# stm32uni.net
KiCad netlist of a schematic drawn in EAGLE
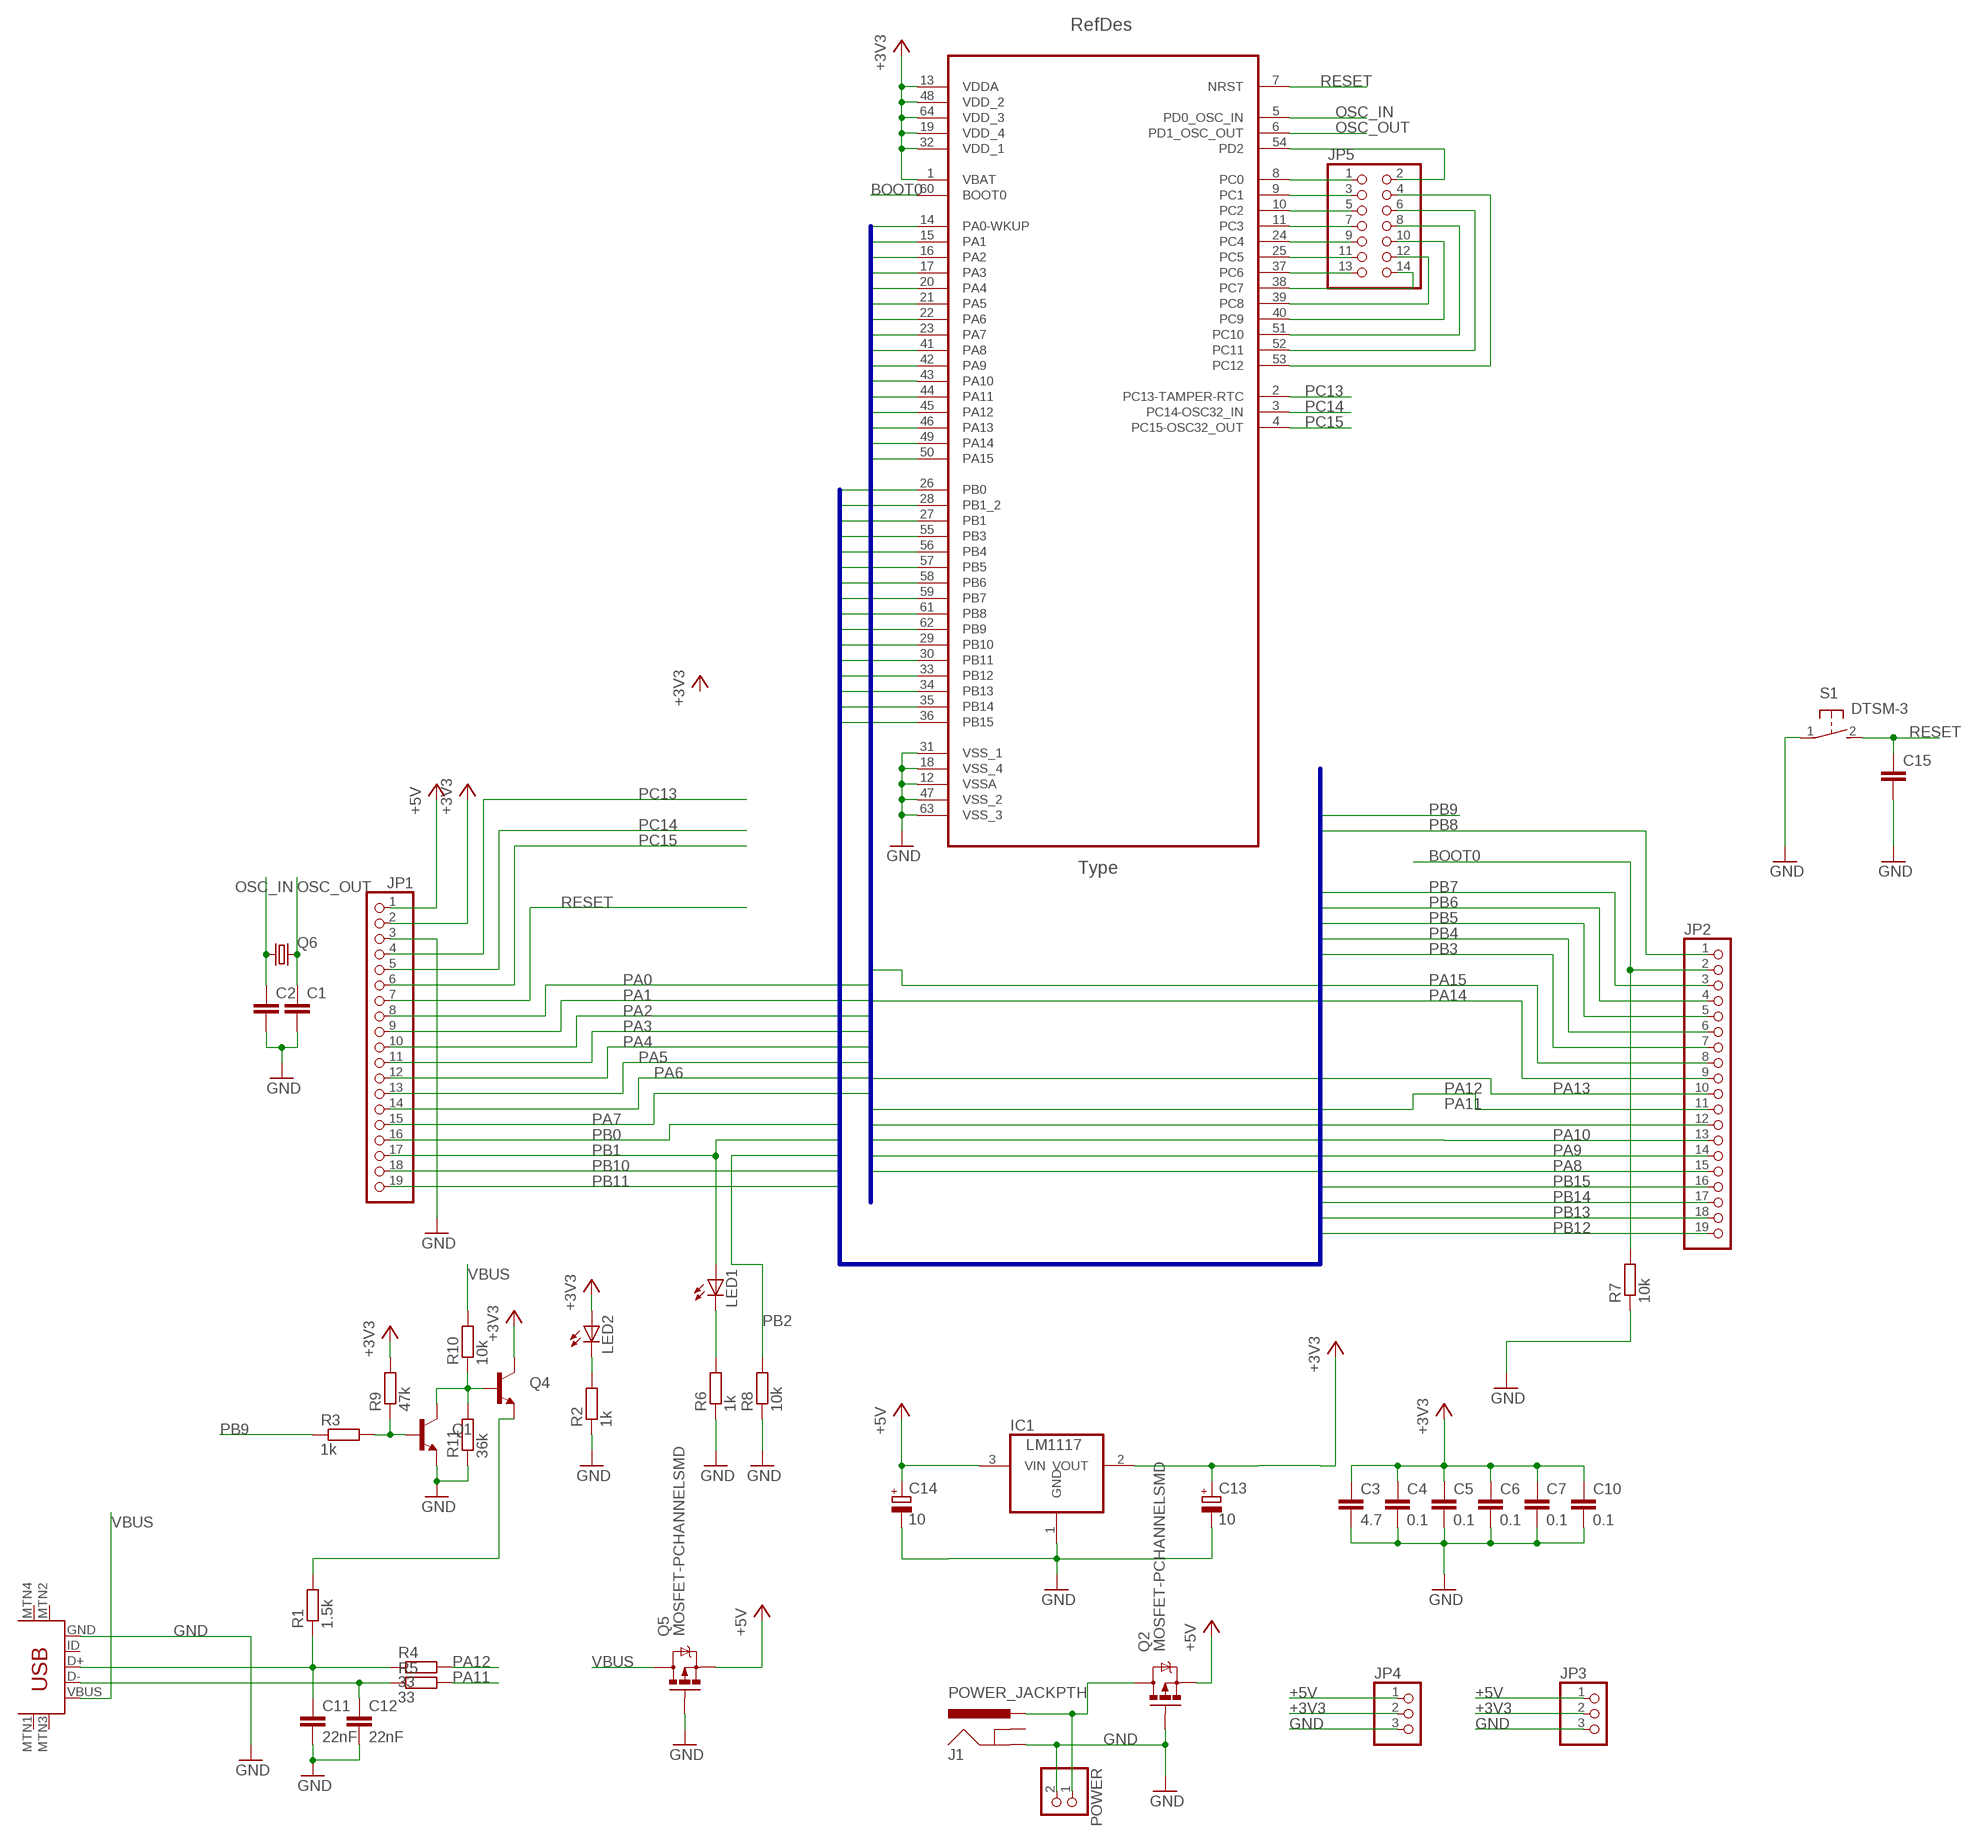
[diagram p0: schematic, sheet 1]

(export (version "E")
  (design (tool "Eeschema 10.0.6"))
  (components
    (comp (ref "C1")
      (value "C-EUC0805")
      (footprint "eagle-import:C0805")
      (libsource (lib "eagle-import") (part "C-EUC0805"))
    )
    (comp (ref "C2")
      (value "C-EUC0805")
      (footprint "eagle-import:C0805")
      (libsource (lib "eagle-import") (part "C-EUC0805"))
    )
    (comp (ref "C3")
      (value "4.7")
      (footprint "eagle-import:C0805")
      (libsource (lib "eagle-import") (part "C-EUC0805"))
    )
    (comp (ref "C4")
      (value "0.1")
      (footprint "eagle-import:C0805")
      (libsource (lib "eagle-import") (part "C-EUC0805"))
    )
    (comp (ref "C5")
      (value "0.1")
      (footprint "eagle-import:C0805")
      (libsource (lib "eagle-import") (part "C-EUC0805"))
    )
    (comp (ref "C6")
      (value "0.1")
      (footprint "eagle-import:C0805")
      (libsource (lib "eagle-import") (part "C-EUC0805"))
    )
    (comp (ref "C7")
      (value "0.1")
      (footprint "eagle-import:C0805")
      (libsource (lib "eagle-import") (part "C-EUC0805"))
    )
    (comp (ref "C10")
      (value "0.1")
      (footprint "eagle-import:C0805")
      (libsource (lib "eagle-import") (part "C-EUC0805"))
    )
    (comp (ref "C11")
      (value "22nF")
      (footprint "eagle-import:C0805")
      (libsource (lib "eagle-import") (part "C-EUC0805"))
    )
    (comp (ref "C12")
      (value "22nF")
      (footprint "eagle-import:C0805")
      (libsource (lib "eagle-import") (part "C-EUC0805"))
    )
    (comp (ref "C13")
      (value "10")
      (footprint "eagle-import:SMC_B")
      (libsource (lib "eagle-import") (part "CPOL-EUSMCB"))
    )
    (comp (ref "C14")
      (value "10")
      (footprint "eagle-import:SMC_B")
      (libsource (lib "eagle-import") (part "CPOL-EUSMCB"))
    )
    (comp (ref "C15")
      (value "C-EUC0805")
      (footprint "eagle-import:C0805")
      (libsource (lib "eagle-import") (part "C-EUC0805"))
    )
    (comp (ref "IC1")
      (value "LM1117")
      (footprint "eagle-import:SOT223")
      (fields (field (name "MPN") "REG1117"))
      (libsource (lib "eagle-import") (part "REG1117"))
    )
    (comp (ref "J1")
      (value "POWER_JACKPTH")
      (footprint "eagle-import:POWER_JACK_PTH")
      (libsource (lib "eagle-import") (part "POWER_JACKPTH"))
    )
    (comp (ref "JP1")
      (value "PINHD-1X19")
      (footprint "eagle-import:1X19")
      (libsource (lib "eagle-import") (part "PINHD-1X19"))
    )
    (comp (ref "JP2")
      (value "PINHD-1X19")
      (footprint "eagle-import:1X19")
      (libsource (lib "eagle-import") (part "PINHD-1X19"))
    )
    (comp (ref "JP3")
      (value "PINHD-1X3")
      (footprint "eagle-import:1X03")
      (libsource (lib "eagle-import") (part "PINHD-1X3"))
    )
    (comp (ref "JP4")
      (value "PINHD-1X3")
      (footprint "eagle-import:1X03")
      (libsource (lib "eagle-import") (part "PINHD-1X3"))
    )
    (comp (ref "JP5")
      (value "PINHD-2X7")
      (footprint "eagle-import:2X07")
      (libsource (lib "eagle-import") (part "PINHD-2X7"))
    )
    (comp (ref "LED1")
      (value "LEDCHIPLED_0805")
      (footprint "eagle-import:CHIPLED_0805")
      (libsource (lib "eagle-import") (part "LEDCHIPLED_0805"))
    )
    (comp (ref "LED2")
      (value "LEDCHIPLED_0805")
      (footprint "eagle-import:CHIPLED_0805")
      (libsource (lib "eagle-import") (part "LEDCHIPLED_0805"))
    )
    (comp (ref "POWER")
      (value "PINHD-1X2")
      (footprint "eagle-import:1X02")
      (libsource (lib "eagle-import") (part "PINHD-1X2"))
    )
    (comp (ref "Q1")
      (value "TRANSISTOR_NPNSOT23")
      (footprint "eagle-import:SOT23")
      (libsource (lib "eagle-import") (part "TRANSISTOR_NPNSOT23"))
    )
    (comp (ref "Q2")
      (value "MOSFET-PCHANNELSMD")
      (footprint "eagle-import:SOT23-3")
      (libsource (lib "eagle-import") (part "MOSFET-PCHANNELSMD"))
    )
    (comp (ref "Q4")
      (value "TRANSISTOR_NPNSOT23")
      (footprint "eagle-import:SOT23")
      (libsource (lib "eagle-import") (part "TRANSISTOR_NPNSOT23"))
    )
    (comp (ref "Q5")
      (value "MOSFET-PCHANNELSMD")
      (footprint "eagle-import:SOT23-3")
      (libsource (lib "eagle-import") (part "MOSFET-PCHANNELSMD"))
    )
    (comp (ref "Q6")
      (value "CRYSTALSM49")
      (footprint "eagle-import:SM49")
      (libsource (lib "eagle-import") (part "CRYSTALSM49"))
    )
    (comp (ref "R1")
      (value "1.5k")
      (footprint "eagle-import:R0805")
      (libsource (lib "eagle-import") (part "R-EU_R0805"))
    )
    (comp (ref "R2")
      (value "1k")
      (footprint "eagle-import:R0805")
      (libsource (lib "eagle-import") (part "R-EU_R0805"))
    )
    (comp (ref "R3")
      (value "1k")
      (footprint "eagle-import:R0805")
      (libsource (lib "eagle-import") (part "R-EU_R0805"))
    )
    (comp (ref "R4")
      (value "33")
      (footprint "eagle-import:R0805")
      (libsource (lib "eagle-import") (part "R-EU_R0805"))
    )
    (comp (ref "R5")
      (value "33")
      (footprint "eagle-import:R0805")
      (libsource (lib "eagle-import") (part "R-EU_R0805"))
    )
    (comp (ref "R6")
      (value "1k")
      (footprint "eagle-import:R0805")
      (libsource (lib "eagle-import") (part "R-EU_R0805"))
    )
    (comp (ref "R7")
      (value "10k")
      (footprint "eagle-import:R0805")
      (libsource (lib "eagle-import") (part "R-EU_R0805"))
    )
    (comp (ref "R8")
      (value "10k")
      (footprint "eagle-import:R0805")
      (libsource (lib "eagle-import") (part "R-EU_R0805"))
    )
    (comp (ref "R9")
      (value "47k")
      (footprint "eagle-import:R0805")
      (libsource (lib "eagle-import") (part "R-EU_R0805"))
    )
    (comp (ref "R10")
      (value "10k")
      (footprint "eagle-import:R0805")
      (libsource (lib "eagle-import") (part "R-EU_R0805"))
    )
    (comp (ref "R11")
      (value "36k")
      (footprint "eagle-import:R0805")
      (libsource (lib "eagle-import") (part "R-EU_R0805"))
    )
    (comp (ref "S1")
      (value "DTSM-3")
      (footprint "eagle-import:DTSM-3")
      (libsource (lib "eagle-import") (part "DTSM-3"))
    )
    (comp (ref "U$1")
      (value "USB-MINIB-5PIN")
      (footprint "eagle-import:USB-MINIB")
      (libsource (lib "eagle-import") (part "USB-MINIB-5PIN"))
    )
    (comp (ref "U1")
      (value "STM32F103RET6")
      (footprint "eagle-import:QFP50P1200X1200X160-64N")
      (libsource (lib "eagle-import") (part "STM32F103RET6"))
    )
  )
  (nets
    (net (code "1") (name "+3V3") (class "Default")
      (node (ref "C10") (pin "1") (pinfunction "1_1") (pintype "passive"))
      (node (ref "C13") (pin "+") (pinfunction "+_+") (pintype "passive"))
      (node (ref "C3") (pin "1") (pinfunction "1_1") (pintype "passive"))
      (node (ref "C4") (pin "1") (pinfunction "1_1") (pintype "passive"))
      (node (ref "C5") (pin "1") (pinfunction "1_1") (pintype "passive"))
      (node (ref "C6") (pin "1") (pinfunction "1_1") (pintype "passive"))
      (node (ref "C7") (pin "1") (pinfunction "1_1") (pintype "passive"))
      (node (ref "IC1") (pin "2") (pinfunction "VOUT_2") (pintype "output"))
      (node (ref "JP1") (pin "2") (pinfunction "2_2") (pintype "passive"))
      (node (ref "JP3") (pin "2") (pinfunction "2_2") (pintype "passive"))
      (node (ref "JP4") (pin "2") (pinfunction "2_2") (pintype "passive"))
      (node (ref "LED2") (pin "A") (pinfunction "A_A") (pintype "passive"))
      (node (ref "Q4") (pin "3") (pinfunction "C_3") (pintype "passive"))
      (node (ref "R9") (pin "2") (pinfunction "2_2") (pintype "passive"))
      (node (ref "U1") (pin "1") (pinfunction "VBAT_1") (pintype "input"))
      (node (ref "U1") (pin "13") (pinfunction "VDDA_13") (pintype "power_in"))
      (node (ref "U1") (pin "19") (pinfunction "VDD_4_19") (pintype "power_in"))
      (node (ref "U1") (pin "32") (pinfunction "VDD_1_32") (pintype "power_in"))
      (node (ref "U1") (pin "48") (pinfunction "VDD_2_48") (pintype "power_in"))
      (node (ref "U1") (pin "64") (pinfunction "VDD_3_64") (pintype "power_in"))
    )
    (net (code "2") (name "+5V") (class "Default")
      (node (ref "C14") (pin "+") (pinfunction "+_+") (pintype "passive"))
      (node (ref "IC1") (pin "3") (pinfunction "VIN_3") (pintype "input"))
      (node (ref "JP1") (pin "1") (pinfunction "1_1") (pintype "passive"))
      (node (ref "JP3") (pin "1") (pinfunction "1_1") (pintype "passive"))
      (node (ref "JP4") (pin "1") (pinfunction "1_1") (pintype "passive"))
      (node (ref "Q2") (pin "2") (pinfunction "S_2") (pintype "passive"))
      (node (ref "Q5") (pin "2") (pinfunction "S_2") (pintype "passive"))
    )
    (net (code "3") (name "/BOOT0") (class "Default")
      (node (ref "JP2") (pin "2") (pinfunction "2_2") (pintype "passive"))
      (node (ref "R7") (pin "2") (pinfunction "2_2") (pintype "passive"))
      (node (ref "U1") (pin "60") (pinfunction "BOOT0_60") (pintype "passive"))
    )
    (net (code "4") (name "/OSC_IN") (class "Default")
      (node (ref "C2") (pin "1") (pinfunction "1_1") (pintype "passive"))
      (node (ref "Q6") (pin "1") (pinfunction "1_1") (pintype "passive"))
      (node (ref "U1") (pin "5") (pinfunction "PD0_OSC_IN_5") (pintype "input"))
    )
    (net (code "5") (name "/OSC_OUT") (class "Default")
      (node (ref "C1") (pin "1") (pinfunction "1_1") (pintype "passive"))
      (node (ref "Q6") (pin "2") (pinfunction "2_2") (pintype "passive"))
      (node (ref "U1") (pin "6") (pinfunction "PD1_OSC_OUT_6") (pintype "output"))
    )
    (net (code "6") (name "/PA0") (class "Default")
      (node (ref "JP1") (pin "8") (pinfunction "8_8") (pintype "passive"))
      (node (ref "U1") (pin "14") (pinfunction "PA0-WKUP_14") (pintype "bidirectional"))
    )
    (net (code "7") (name "/PA1") (class "Default")
      (node (ref "JP1") (pin "9") (pinfunction "9_9") (pintype "passive"))
      (node (ref "U1") (pin "15") (pinfunction "PA1_15") (pintype "bidirectional"))
    )
    (net (code "8") (name "/PA2") (class "Default")
      (node (ref "JP1") (pin "10") (pinfunction "10_10") (pintype "passive"))
      (node (ref "U1") (pin "16") (pinfunction "PA2_16") (pintype "bidirectional"))
    )
    (net (code "9") (name "/PA3") (class "Default")
      (node (ref "JP1") (pin "11") (pinfunction "11_11") (pintype "passive"))
      (node (ref "U1") (pin "17") (pinfunction "PA3_17") (pintype "bidirectional"))
    )
    (net (code "10") (name "/PA4") (class "Default")
      (node (ref "JP1") (pin "12") (pinfunction "12_12") (pintype "passive"))
      (node (ref "U1") (pin "20") (pinfunction "PA4_20") (pintype "bidirectional"))
    )
    (net (code "11") (name "/PA5") (class "Default")
      (node (ref "JP1") (pin "13") (pinfunction "13_13") (pintype "passive"))
      (node (ref "U1") (pin "21") (pinfunction "PA5_21") (pintype "bidirectional"))
    )
    (net (code "12") (name "/PA6") (class "Default")
      (node (ref "JP1") (pin "14") (pinfunction "14_14") (pintype "passive"))
      (node (ref "U1") (pin "22") (pinfunction "PA6_22") (pintype "bidirectional"))
    )
    (net (code "13") (name "/PA7") (class "Default")
      (node (ref "JP1") (pin "15") (pinfunction "15_15") (pintype "passive"))
      (node (ref "U1") (pin "23") (pinfunction "PA7_23") (pintype "power_in"))
    )
    (net (code "14") (name "/PA8") (class "Default")
      (node (ref "JP2") (pin "15") (pinfunction "15_15") (pintype "passive"))
      (node (ref "U1") (pin "41") (pinfunction "PA8_41") (pintype "bidirectional"))
    )
    (net (code "15") (name "/PA9") (class "Default")
      (node (ref "JP2") (pin "14") (pinfunction "14_14") (pintype "passive"))
      (node (ref "U1") (pin "42") (pinfunction "PA9_42") (pintype "bidirectional"))
    )
    (net (code "16") (name "/PA10") (class "Default")
      (node (ref "JP2") (pin "13") (pinfunction "13_13") (pintype "passive"))
      (node (ref "U1") (pin "43") (pinfunction "PA10_43") (pintype "bidirectional"))
    )
    (net (code "17") (name "/PA11") (class "Default")
      (node (ref "JP2") (pin "12") (pinfunction "12_12") (pintype "passive"))
      (node (ref "R5") (pin "2") (pinfunction "2_2") (pintype "passive"))
      (node (ref "U1") (pin "44") (pinfunction "PA11_44") (pintype "bidirectional"))
    )
    (net (code "18") (name "/PA12") (class "Default")
      (node (ref "JP2") (pin "11") (pinfunction "11_11") (pintype "passive"))
      (node (ref "R4") (pin "2") (pinfunction "2_2") (pintype "passive"))
      (node (ref "U1") (pin "45") (pinfunction "PA12_45") (pintype "bidirectional"))
    )
    (net (code "19") (name "/PA13") (class "Default")
      (node (ref "JP2") (pin "10") (pinfunction "10_10") (pintype "passive"))
      (node (ref "U1") (pin "46") (pinfunction "PA13_46") (pintype "bidirectional"))
    )
    (net (code "20") (name "/PA14") (class "Default")
      (node (ref "JP2") (pin "9") (pinfunction "9_9") (pintype "passive"))
      (node (ref "U1") (pin "49") (pinfunction "PA14_49") (pintype "bidirectional"))
    )
    (net (code "21") (name "/PA15") (class "Default")
      (node (ref "JP2") (pin "8") (pinfunction "8_8") (pintype "passive"))
      (node (ref "U1") (pin "50") (pinfunction "PA15_50") (pintype "bidirectional"))
    )
    (net (code "22") (name "/PB0") (class "Default")
      (node (ref "JP1") (pin "16") (pinfunction "16_16") (pintype "passive"))
      (node (ref "U1") (pin "26") (pinfunction "PB0_26") (pintype "bidirectional"))
    )
    (net (code "23") (name "/PB1") (class "Default")
      (node (ref "JP1") (pin "17") (pinfunction "17_17") (pintype "passive"))
      (node (ref "LED1") (pin "A") (pinfunction "A_A") (pintype "passive"))
      (node (ref "U1") (pin "27") (pinfunction "PB1_27") (pintype "bidirectional"))
    )
    (net (code "24") (name "/PB2") (class "Default")
      (node (ref "R8") (pin "2") (pinfunction "2_2") (pintype "passive"))
      (node (ref "U1") (pin "28") (pinfunction "PB1_2_28") (pintype "bidirectional"))
    )
    (net (code "25") (name "/PB3") (class "Default")
      (node (ref "JP2") (pin "7") (pinfunction "7_7") (pintype "passive"))
      (node (ref "U1") (pin "55") (pinfunction "PB3_55") (pintype "bidirectional"))
    )
    (net (code "26") (name "/PB4") (class "Default")
      (node (ref "JP2") (pin "6") (pinfunction "6_6") (pintype "passive"))
      (node (ref "U1") (pin "56") (pinfunction "PB4_56") (pintype "bidirectional"))
    )
    (net (code "27") (name "/PB5") (class "Default")
      (node (ref "JP2") (pin "5") (pinfunction "5_5") (pintype "passive"))
      (node (ref "U1") (pin "57") (pinfunction "PB5_57") (pintype "bidirectional"))
    )
    (net (code "28") (name "/PB6") (class "Default")
      (node (ref "JP2") (pin "4") (pinfunction "4_4") (pintype "passive"))
      (node (ref "U1") (pin "58") (pinfunction "PB6_58") (pintype "bidirectional"))
    )
    (net (code "29") (name "/PB7") (class "Default")
      (node (ref "JP2") (pin "3") (pinfunction "3_3") (pintype "passive"))
      (node (ref "U1") (pin "59") (pinfunction "PB7_59") (pintype "power_in"))
    )
    (net (code "30") (name "/PB8") (class "Default")
      (node (ref "JP2") (pin "1") (pinfunction "1_1") (pintype "passive"))
      (node (ref "U1") (pin "61") (pinfunction "PB8_61") (pintype "bidirectional"))
    )
    (net (code "31") (name "/PB9") (class "Default")
      (node (ref "R3") (pin "1") (pinfunction "1_1") (pintype "passive"))
      (node (ref "U1") (pin "62") (pinfunction "PB9_62") (pintype "bidirectional"))
    )
    (net (code "32") (name "/PB10") (class "Default")
      (node (ref "JP1") (pin "18") (pinfunction "18_18") (pintype "passive"))
      (node (ref "U1") (pin "29") (pinfunction "PB10_29") (pintype "bidirectional"))
    )
    (net (code "33") (name "/PB11") (class "Default")
      (node (ref "JP1") (pin "19") (pinfunction "19_19") (pintype "passive"))
      (node (ref "U1") (pin "30") (pinfunction "PB11_30") (pintype "bidirectional"))
    )
    (net (code "34") (name "/PB12") (class "Default")
      (node (ref "JP2") (pin "19") (pinfunction "19_19") (pintype "passive"))
      (node (ref "U1") (pin "33") (pinfunction "PB12_33") (pintype "bidirectional"))
    )
    (net (code "35") (name "/PB13") (class "Default")
      (node (ref "JP2") (pin "18") (pinfunction "18_18") (pintype "passive"))
      (node (ref "U1") (pin "34") (pinfunction "PB13_34") (pintype "bidirectional"))
    )
    (net (code "36") (name "/PB14") (class "Default")
      (node (ref "JP2") (pin "17") (pinfunction "17_17") (pintype "passive"))
      (node (ref "U1") (pin "35") (pinfunction "PB14_35") (pintype "bidirectional"))
    )
    (net (code "37") (name "/PB15") (class "Default")
      (node (ref "JP2") (pin "16") (pinfunction "16_16") (pintype "passive"))
      (node (ref "U1") (pin "36") (pinfunction "PB15_36") (pintype "bidirectional"))
    )
    (net (code "38") (name "/PC13") (class "Default")
      (node (ref "JP1") (pin "4") (pinfunction "4_4") (pintype "passive"))
      (node (ref "U1") (pin "2") (pinfunction "PC13-TAMPER-RTC_2") (pintype "input"))
    )
    (net (code "39") (name "/PC14") (class "Default")
      (node (ref "JP1") (pin "5") (pinfunction "5_5") (pintype "passive"))
      (node (ref "U1") (pin "3") (pinfunction "PC14-OSC32_IN_3") (pintype "input"))
    )
    (net (code "40") (name "/PC15") (class "Default")
      (node (ref "JP1") (pin "6") (pinfunction "6_6") (pintype "passive"))
      (node (ref "U1") (pin "4") (pinfunction "PC15-OSC32_OUT_4") (pintype "output"))
    )
    (net (code "41") (name "/RESET") (class "Default")
      (node (ref "C15") (pin "1") (pinfunction "1_1") (pintype "passive"))
      (node (ref "JP1") (pin "7") (pinfunction "7_7") (pintype "passive"))
      (node (ref "S1") (pin "2") (pinfunction "2_2") (pintype "passive"))
      (node (ref "U1") (pin "7") (pinfunction "NRST_7") (pintype "output"))
    )
    (net (code "42") (name "/VBUS") (class "Default")
      (node (ref "Q5") (pin "3") (pinfunction "D_3") (pintype "passive"))
      (node (ref "R10") (pin "2") (pinfunction "2_2") (pintype "passive"))
      (node (ref "U$1") (pin "VBUS") (pinfunction "VBUS_VBUS") (pintype "bidirectional"))
    )
    (net (code "43") (name "GND") (class "Default")
      (node (ref "C1") (pin "2") (pinfunction "2_2") (pintype "passive"))
      (node (ref "C10") (pin "2") (pinfunction "2_2") (pintype "passive"))
      (node (ref "C11") (pin "2") (pinfunction "2_2") (pintype "passive"))
      (node (ref "C12") (pin "2") (pinfunction "2_2") (pintype "passive"))
      (node (ref "C13") (pin "-") (pinfunction "-_-") (pintype "passive"))
      (node (ref "C14") (pin "-") (pinfunction "-_-") (pintype "passive"))
      (node (ref "C15") (pin "2") (pinfunction "2_2") (pintype "passive"))
      (node (ref "C2") (pin "2") (pinfunction "2_2") (pintype "passive"))
      (node (ref "C3") (pin "2") (pinfunction "2_2") (pintype "passive"))
      (node (ref "C4") (pin "2") (pinfunction "2_2") (pintype "passive"))
      (node (ref "C5") (pin "2") (pinfunction "2_2") (pintype "passive"))
      (node (ref "C6") (pin "2") (pinfunction "2_2") (pintype "passive"))
      (node (ref "C7") (pin "2") (pinfunction "2_2") (pintype "passive"))
      (node (ref "IC1") (pin "1") (pinfunction "GND_1") (pintype "power_in"))
      (node (ref "J1") (pin "GND") (pinfunction "GND_GND") (pintype "bidirectional"))
      (node (ref "JP1") (pin "3") (pinfunction "3_3") (pintype "passive"))
      (node (ref "JP3") (pin "3") (pinfunction "3_3") (pintype "passive"))
      (node (ref "JP4") (pin "3") (pinfunction "3_3") (pintype "passive"))
      (node (ref "POWER") (pin "2") (pinfunction "2_2") (pintype "passive"))
      (node (ref "Q1") (pin "2") (pinfunction "E_2") (pintype "passive"))
      (node (ref "Q2") (pin "1") (pinfunction "G_1") (pintype "passive"))
      (node (ref "Q5") (pin "1") (pinfunction "G_1") (pintype "passive"))
      (node (ref "R11") (pin "1") (pinfunction "1_1") (pintype "passive"))
      (node (ref "R2") (pin "1") (pinfunction "1_1") (pintype "passive"))
      (node (ref "R6") (pin "1") (pinfunction "1_1") (pintype "passive"))
      (node (ref "R7") (pin "1") (pinfunction "1_1") (pintype "passive"))
      (node (ref "R8") (pin "1") (pinfunction "1_1") (pintype "passive"))
      (node (ref "S1") (pin "1") (pinfunction "1_1") (pintype "passive"))
      (node (ref "U$1") (pin "GND") (pinfunction "GND_GND") (pintype "bidirectional"))
      (node (ref "U1") (pin "12") (pinfunction "VSSA_12") (pintype "passive"))
      (node (ref "U1") (pin "18") (pinfunction "VSS_4_18") (pintype "passive"))
      (node (ref "U1") (pin "31") (pinfunction "VSS_1_31") (pintype "passive"))
      (node (ref "U1") (pin "47") (pinfunction "VSS_2_47") (pintype "passive"))
      (node (ref "U1") (pin "63") (pinfunction "VSS_3_63") (pintype "passive"))
    )
    (net (code "44") (name "Net-(C11-Pad1)") (class "Default")
      (node (ref "C11") (pin "1") (pinfunction "1_1") (pintype "passive"))
      (node (ref "R1") (pin "1") (pinfunction "1_1") (pintype "passive"))
      (node (ref "R4") (pin "1") (pinfunction "1_1") (pintype "passive"))
      (node (ref "U$1") (pin "D+") (pinfunction "D+_D+") (pintype "bidirectional"))
    )
    (net (code "45") (name "Net-(C12-Pad1)") (class "Default")
      (node (ref "C12") (pin "1") (pinfunction "1_1") (pintype "passive"))
      (node (ref "R5") (pin "1") (pinfunction "1_1") (pintype "passive"))
      (node (ref "U$1") (pin "D-") (pinfunction "D-_D-") (pintype "bidirectional"))
    )
    (net (code "46") (name "Net-(LED1-PadC)") (class "Default")
      (node (ref "LED1") (pin "C") (pinfunction "C_C") (pintype "passive"))
      (node (ref "R6") (pin "2") (pinfunction "2_2") (pintype "passive"))
    )
    (net (code "47") (name "Net-(LED2-PadC)") (class "Default")
      (node (ref "LED2") (pin "C") (pinfunction "C_C") (pintype "passive"))
      (node (ref "R2") (pin "2") (pinfunction "2_2") (pintype "passive"))
    )
    (net (code "48") (name "Net-(Q1-B)") (class "Default")
      (node (ref "Q1") (pin "1") (pinfunction "B_1") (pintype "passive"))
      (node (ref "R3") (pin "2") (pinfunction "2_2") (pintype "passive"))
      (node (ref "R9") (pin "1") (pinfunction "1_1") (pintype "passive"))
    )
    (net (code "49") (name "Net-(Q1-C)") (class "Default")
      (node (ref "Q1") (pin "3") (pinfunction "C_3") (pintype "passive"))
      (node (ref "Q4") (pin "1") (pinfunction "B_1") (pintype "passive"))
      (node (ref "R10") (pin "1") (pinfunction "1_1") (pintype "passive"))
      (node (ref "R11") (pin "2") (pinfunction "2_2") (pintype "passive"))
    )
    (net (code "50") (name "Net-(Q2-D)") (class "Default")
      (node (ref "J1") (pin "PWR") (pinfunction "PWR_PWR") (pintype "bidirectional"))
      (node (ref "POWER") (pin "1") (pinfunction "1_1") (pintype "passive"))
      (node (ref "Q2") (pin "3") (pinfunction "D_3") (pintype "passive"))
    )
    (net (code "51") (name "Net-(Q4-E)") (class "Default")
      (node (ref "Q4") (pin "2") (pinfunction "E_2") (pintype "passive"))
      (node (ref "R1") (pin "2") (pinfunction "2_2") (pintype "passive"))
    )
    (net (code "52") (name "Net-(U1-PC0)") (class "Default")
      (node (ref "JP5") (pin "1") (pinfunction "1_1") (pintype "passive"))
      (node (ref "U1") (pin "8") (pinfunction "PC0_8") (pintype "bidirectional"))
    )
    (net (code "53") (name "Net-(U1-PC1)") (class "Default")
      (node (ref "JP5") (pin "3") (pinfunction "3_3") (pintype "passive"))
      (node (ref "U1") (pin "9") (pinfunction "PC1_9") (pintype "bidirectional"))
    )
    (net (code "54") (name "Net-(U1-PC2)") (class "Default")
      (node (ref "JP5") (pin "5") (pinfunction "5_5") (pintype "passive"))
      (node (ref "U1") (pin "10") (pinfunction "PC2_10") (pintype "bidirectional"))
    )
    (net (code "55") (name "Net-(U1-PC3)") (class "Default")
      (node (ref "JP5") (pin "7") (pinfunction "7_7") (pintype "passive"))
      (node (ref "U1") (pin "11") (pinfunction "PC3_11") (pintype "bidirectional"))
    )
    (net (code "56") (name "Net-(U1-PC4)") (class "Default")
      (node (ref "JP5") (pin "9") (pinfunction "9_9") (pintype "passive"))
      (node (ref "U1") (pin "24") (pinfunction "PC4_24") (pintype "passive"))
    )
    (net (code "57") (name "Net-(U1-PC5)") (class "Default")
      (node (ref "JP5") (pin "11") (pinfunction "11_11") (pintype "passive"))
      (node (ref "U1") (pin "25") (pinfunction "PC5_25") (pintype "bidirectional"))
    )
    (net (code "58") (name "Net-(U1-PC6)") (class "Default")
      (node (ref "JP5") (pin "13") (pinfunction "13_13") (pintype "passive"))
      (node (ref "U1") (pin "37") (pinfunction "PC6_37") (pintype "bidirectional"))
    )
    (net (code "59") (name "Net-(U1-PC7)") (class "Default")
      (node (ref "JP5") (pin "14") (pinfunction "14_14") (pintype "passive"))
      (node (ref "U1") (pin "38") (pinfunction "PC7_38") (pintype "bidirectional"))
    )
    (net (code "60") (name "Net-(U1-PC8)") (class "Default")
      (node (ref "JP5") (pin "12") (pinfunction "12_12") (pintype "passive"))
      (node (ref "U1") (pin "39") (pinfunction "PC8_39") (pintype "bidirectional"))
    )
    (net (code "61") (name "Net-(U1-PC9)") (class "Default")
      (node (ref "JP5") (pin "10") (pinfunction "10_10") (pintype "passive"))
      (node (ref "U1") (pin "40") (pinfunction "PC9_40") (pintype "bidirectional"))
    )
    (net (code "62") (name "Net-(U1-PC10)") (class "Default")
      (node (ref "JP5") (pin "8") (pinfunction "8_8") (pintype "passive"))
      (node (ref "U1") (pin "51") (pinfunction "PC10_51") (pintype "bidirectional"))
    )
    (net (code "63") (name "Net-(U1-PC11)") (class "Default")
      (node (ref "JP5") (pin "6") (pinfunction "6_6") (pintype "passive"))
      (node (ref "U1") (pin "52") (pinfunction "PC11_52") (pintype "bidirectional"))
    )
    (net (code "64") (name "Net-(U1-PC12)") (class "Default")
      (node (ref "JP5") (pin "4") (pinfunction "4_4") (pintype "passive"))
      (node (ref "U1") (pin "53") (pinfunction "PC12_53") (pintype "bidirectional"))
    )
    (net (code "65") (name "Net-(U1-PD2)") (class "Default")
      (node (ref "JP5") (pin "2") (pinfunction "2_2") (pintype "passive"))
      (node (ref "U1") (pin "54") (pinfunction "PD2_54") (pintype "bidirectional"))
    )
    (net (code "66") (name "unconnected-(J1-PadGNDBREAK)") (class "Default")
      (node (ref "J1") (pin "GNDBREAK") (pinfunction "GNDBREAK_GNDBREAK") (pintype "bidirectional"))
    )
    (net (code "67") (name "unconnected-(U$1-MTN1-PadMTN3)") (class "Default")
      (node (ref "U$1") (pin "MTN3") (pinfunction "MTN1_MTN3") (pintype "bidirectional"))
    )
    (net (code "68") (name "unconnected-(U$1-MTN2-PadMTN1)") (class "Default")
      (node (ref "U$1") (pin "MTN1") (pinfunction "MTN2_MTN1") (pintype "bidirectional"))
    )
    (net (code "69") (name "unconnected-(U$1-MTN3-PadMTN2)") (class "Default")
      (node (ref "U$1") (pin "MTN2") (pinfunction "MTN3_MTN2") (pintype "bidirectional"))
    )
    (net (code "70") (name "unconnected-(U$1-PadID)") (class "Default")
      (node (ref "U$1") (pin "ID") (pinfunction "ID_ID") (pintype "bidirectional"))
    )
    (net (code "71") (name "unconnected-(U$1-PadMTN4)") (class "Default")
      (node (ref "U$1") (pin "MTN4") (pinfunction "MTN4_MTN4") (pintype "bidirectional"))
    )
  )
)
